# Mother_Board_STM32.net
KiCad netlist of a schematic drawn in Altium Designer
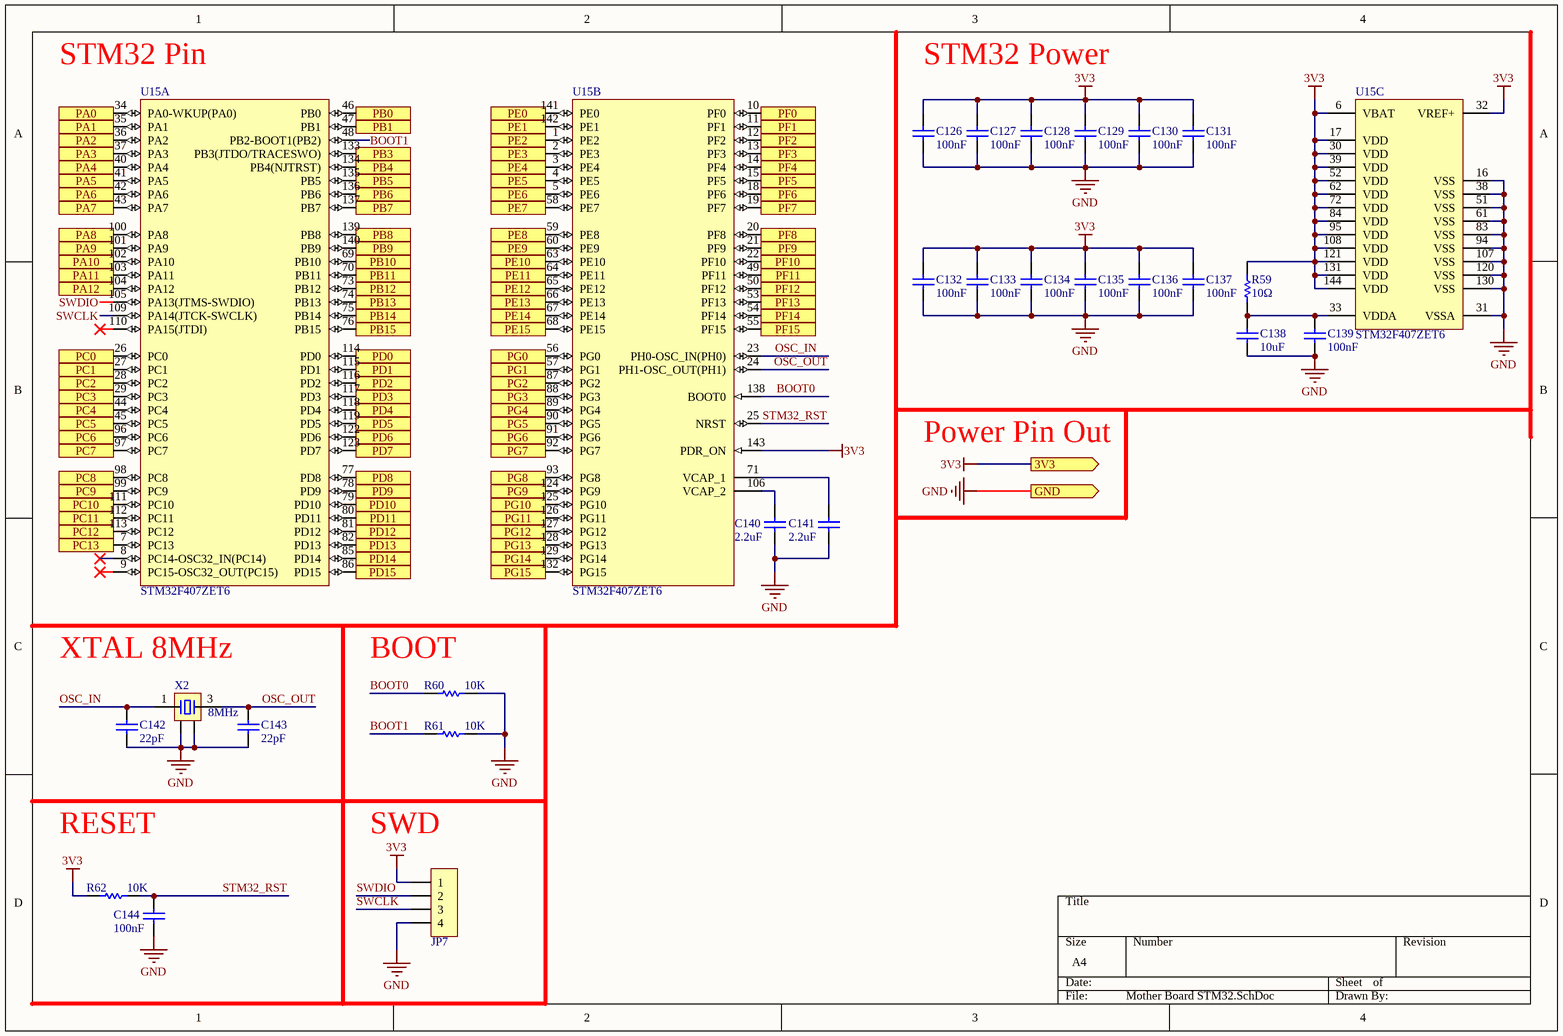
[diagram p0: Mother Board STM32.SchDoc]

(export (version "E")
  (design (tool "Eeschema 10.0.6"))
  (components
    (comp (ref "C126") (value "100nF") (footprint "C0402") (libsource (lib "Cap") (part "Cap")))
    (comp (ref "C127") (value "100nF") (footprint "C0402") (libsource (lib "Cap") (part "Cap")))
    (comp (ref "C128") (value "100nF") (footprint "C0402") (libsource (lib "Cap") (part "Cap")))
    (comp (ref "C129") (value "100nF") (footprint "C0402") (libsource (lib "Cap") (part "Cap")))
    (comp (ref "C130") (value "100nF") (footprint "C0402") (libsource (lib "Cap") (part "Cap")))
    (comp (ref "C131") (value "100nF") (footprint "C0402") (libsource (lib "Cap") (part "Cap")))
    (comp (ref "C132") (value "100nF") (footprint "C0402") (libsource (lib "Cap") (part "Cap")))
    (comp (ref "C133") (value "100nF") (footprint "C0402") (libsource (lib "Cap") (part "Cap")))
    (comp (ref "C134") (value "100nF") (footprint "C0402") (libsource (lib "Cap") (part "Cap")))
    (comp (ref "C135") (value "100nF") (footprint "C0402") (libsource (lib "Cap") (part "Cap")))
    (comp (ref "C136") (value "100nF") (footprint "C0402") (libsource (lib "Cap") (part "Cap")))
    (comp (ref "C137") (value "100nF") (footprint "C0402") (libsource (lib "Cap") (part "Cap")))
    (comp (ref "C138") (value "10uF") (footprint "C0805") (libsource (lib "Cap") (part "Cap")))
    (comp (ref "C139") (value "100nF") (footprint "C0402") (libsource (lib "Cap") (part "Cap")))
    (comp (ref "C140") (value "2.2uF") (footprint "C0603") (libsource (lib "Cap") (part "Cap")))
    (comp (ref "C141") (value "2.2uF") (footprint "C0603") (libsource (lib "Cap") (part "Cap")))
    (comp (ref "C142") (value "22pF") (footprint "C0603") (libsource (lib "Cap") (part "Cap")))
    (comp (ref "C143") (value "22pF") (footprint "C0603") (libsource (lib "Cap") (part "Cap")))
    (comp (ref "C144") (value "100nF") (footprint "C0402") (libsource (lib "Cap") (part "Cap")))
    (comp (ref "JP7")
      (value "HDR-1X4")
      (footprint "XH2.54-4P_H")
      (description "4P接插件")
      (fields (field (name "版权归属") "源创客"))
      (libsource (lib "All lib") (part "Header 4P"))
    )
    (comp (ref "R59") (value "10Ω") (footprint "R0402") (libsource (lib "Res") (part "RES")))
    (comp (ref "R60") (value "10K") (footprint "R0402") (libsource (lib "Res") (part "RES")))
    (comp (ref "R61") (value "10K") (footprint "R0402") (libsource (lib "Res") (part "RES")))
    (comp (ref "R62") (value "10K") (footprint "R0402") (libsource (lib "Res") (part "RES")))
    (comp (ref "U15")
      (value "STM32F407ZET6")
      (footprint "LQFP144 20X20_L")
      (fields (field (name "MANUFACTURER") "STMicroelectronics"))
      (libsource (lib "All lib") (part "STM32F407ZET6"))
    )
    (comp (ref "X2")
      (value "8MHz")
      (footprint "XTAL-3225")
      (description "4脚晶振")
      (fields (field (name "版权归属") "源创客"))
      (libsource (lib "All lib") (part "XTAL-4"))
    )
  )
  (nets
    (net (code "1") (name "/BOOT0") (class "Default")
      (node (ref "R60") (pin "1") (pinfunction "1_1") (pintype "passive"))
      (node (ref "U15") (pin "138") (pinfunction "BOOT0_138") (pintype "input"))
    )
    (net (code "2") (name "/BOOT1") (class "Default")
      (node (ref "R61") (pin "1") (pinfunction "1_1") (pintype "passive"))
      (node (ref "U15") (pin "48") (pinfunction "PB2-BOOT1(PB2)_48") (pintype "bidirectional"))
    )
    (net (code "3") (name "/OSC_IN") (class "Default")
      (node (ref "C142") (pin "2") (pinfunction "2_2") (pintype "passive"))
      (node (ref "U15") (pin "23") (pinfunction "PH0-OSC_IN(PH0)_23") (pintype "bidirectional"))
      (node (ref "X2") (pin "1") (pinfunction "1_1") (pintype "passive"))
    )
    (net (code "4") (name "/OSC_OUT") (class "Default")
      (node (ref "C143") (pin "2") (pinfunction "2_2") (pintype "passive"))
      (node (ref "U15") (pin "24") (pinfunction "PH1-OSC_OUT(PH1)_24") (pintype "bidirectional"))
      (node (ref "X2") (pin "3") (pinfunction "3_3") (pintype "passive"))
    )
    (net (code "5") (name "/PA0") (class "Default")
      (node (ref "U15") (pin "34") (pinfunction "PA0-WKUP(PA0)_34") (pintype "bidirectional"))
    )
    (net (code "6") (name "/PA1") (class "Default")
      (node (ref "U15") (pin "35") (pinfunction "PA1_35") (pintype "bidirectional"))
    )
    (net (code "7") (name "/PA2") (class "Default")
      (node (ref "U15") (pin "36") (pinfunction "PA2_36") (pintype "bidirectional"))
    )
    (net (code "8") (name "/PA3") (class "Default")
      (node (ref "U15") (pin "37") (pinfunction "PA3_37") (pintype "bidirectional"))
    )
    (net (code "9") (name "/PA4") (class "Default")
      (node (ref "U15") (pin "40") (pinfunction "PA4_40") (pintype "bidirectional"))
    )
    (net (code "10") (name "/PA5") (class "Default")
      (node (ref "U15") (pin "41") (pinfunction "PA5_41") (pintype "bidirectional"))
    )
    (net (code "11") (name "/PA6") (class "Default")
      (node (ref "U15") (pin "42") (pinfunction "PA6_42") (pintype "bidirectional"))
    )
    (net (code "12") (name "/PA7") (class "Default")
      (node (ref "U15") (pin "43") (pinfunction "PA7_43") (pintype "bidirectional"))
    )
    (net (code "13") (name "/PA8") (class "Default")
      (node (ref "U15") (pin "100") (pinfunction "PA8_100") (pintype "bidirectional"))
    )
    (net (code "14") (name "/PA9") (class "Default")
      (node (ref "U15") (pin "101") (pinfunction "PA9_101") (pintype "bidirectional"))
    )
    (net (code "15") (name "/PA10") (class "Default")
      (node (ref "U15") (pin "102") (pinfunction "PA10_102") (pintype "bidirectional"))
    )
    (net (code "16") (name "/PA11") (class "Default")
      (node (ref "U15") (pin "103") (pinfunction "PA11_103") (pintype "bidirectional"))
    )
    (net (code "17") (name "/PA12") (class "Default")
      (node (ref "U15") (pin "104") (pinfunction "PA12_104") (pintype "bidirectional"))
    )
    (net (code "18") (name "/PB0") (class "Default")
      (node (ref "U15") (pin "46") (pinfunction "PB0_46") (pintype "bidirectional"))
    )
    (net (code "19") (name "/PB1") (class "Default")
      (node (ref "U15") (pin "47") (pinfunction "PB1_47") (pintype "bidirectional"))
    )
    (net (code "20") (name "/PB3") (class "Default")
      (node (ref "U15") (pin "133") (pinfunction "PB3(JTDO/TRACESWO)_133") (pintype "bidirectional"))
    )
    (net (code "21") (name "/PB4") (class "Default")
      (node (ref "U15") (pin "134") (pinfunction "PB4(NJTRST)_134") (pintype "bidirectional"))
    )
    (net (code "22") (name "/PB5") (class "Default")
      (node (ref "U15") (pin "135") (pinfunction "PB5_135") (pintype "bidirectional"))
    )
    (net (code "23") (name "/PB6") (class "Default")
      (node (ref "U15") (pin "136") (pinfunction "PB6_136") (pintype "bidirectional"))
    )
    (net (code "24") (name "/PB7") (class "Default")
      (node (ref "U15") (pin "137") (pinfunction "PB7_137") (pintype "bidirectional"))
    )
    (net (code "25") (name "/PB8") (class "Default")
      (node (ref "U15") (pin "139") (pinfunction "PB8_139") (pintype "bidirectional"))
    )
    (net (code "26") (name "/PB9") (class "Default")
      (node (ref "U15") (pin "140") (pinfunction "PB9_140") (pintype "bidirectional"))
    )
    (net (code "27") (name "/PB10") (class "Default")
      (node (ref "U15") (pin "69") (pinfunction "PB10_69") (pintype "bidirectional"))
    )
    (net (code "28") (name "/PB11") (class "Default")
      (node (ref "U15") (pin "70") (pinfunction "PB11_70") (pintype "bidirectional"))
    )
    (net (code "29") (name "/PB12") (class "Default")
      (node (ref "U15") (pin "73") (pinfunction "PB12_73") (pintype "bidirectional"))
    )
    (net (code "30") (name "/PB13") (class "Default")
      (node (ref "U15") (pin "74") (pinfunction "PB13_74") (pintype "bidirectional"))
    )
    (net (code "31") (name "/PB14") (class "Default")
      (node (ref "U15") (pin "75") (pinfunction "PB14_75") (pintype "bidirectional"))
    )
    (net (code "32") (name "/PB15") (class "Default")
      (node (ref "U15") (pin "76") (pinfunction "PB15_76") (pintype "bidirectional"))
    )
    (net (code "33") (name "/PC0") (class "Default")
      (node (ref "U15") (pin "26") (pinfunction "PC0_26") (pintype "bidirectional"))
    )
    (net (code "34") (name "/PC1") (class "Default")
      (node (ref "U15") (pin "27") (pinfunction "PC1_27") (pintype "bidirectional"))
    )
    (net (code "35") (name "/PC2") (class "Default")
      (node (ref "U15") (pin "28") (pinfunction "PC2_28") (pintype "bidirectional"))
    )
    (net (code "36") (name "/PC3") (class "Default")
      (node (ref "U15") (pin "29") (pinfunction "PC3_29") (pintype "bidirectional"))
    )
    (net (code "37") (name "/PC4") (class "Default")
      (node (ref "U15") (pin "44") (pinfunction "PC4_44") (pintype "bidirectional"))
    )
    (net (code "38") (name "/PC5") (class "Default")
      (node (ref "U15") (pin "45") (pinfunction "PC5_45") (pintype "bidirectional"))
    )
    (net (code "39") (name "/PC6") (class "Default")
      (node (ref "U15") (pin "96") (pinfunction "PC6_96") (pintype "bidirectional"))
    )
    (net (code "40") (name "/PC7") (class "Default")
      (node (ref "U15") (pin "97") (pinfunction "PC7_97") (pintype "bidirectional"))
    )
    (net (code "41") (name "/PC8") (class "Default")
      (node (ref "U15") (pin "98") (pinfunction "PC8_98") (pintype "bidirectional"))
    )
    (net (code "42") (name "/PC9") (class "Default")
      (node (ref "U15") (pin "99") (pinfunction "PC9_99") (pintype "bidirectional"))
    )
    (net (code "43") (name "/PC10") (class "Default")
      (node (ref "U15") (pin "111") (pinfunction "PC10_111") (pintype "bidirectional"))
    )
    (net (code "44") (name "/PC11") (class "Default")
      (node (ref "U15") (pin "112") (pinfunction "PC11_112") (pintype "bidirectional"))
    )
    (net (code "45") (name "/PC12") (class "Default")
      (node (ref "U15") (pin "113") (pinfunction "PC12_113") (pintype "bidirectional"))
    )
    (net (code "46") (name "/PC13") (class "Default")
      (node (ref "U15") (pin "7") (pinfunction "PC13_7") (pintype "bidirectional"))
    )
    (net (code "47") (name "/PD0") (class "Default")
      (node (ref "U15") (pin "114") (pinfunction "PD0_114") (pintype "bidirectional"))
    )
    (net (code "48") (name "/PD1") (class "Default")
      (node (ref "U15") (pin "115") (pinfunction "PD1_115") (pintype "bidirectional"))
    )
    (net (code "49") (name "/PD2") (class "Default")
      (node (ref "U15") (pin "116") (pinfunction "PD2_116") (pintype "bidirectional"))
    )
    (net (code "50") (name "/PD3") (class "Default")
      (node (ref "U15") (pin "117") (pinfunction "PD3_117") (pintype "bidirectional"))
    )
    (net (code "51") (name "/PD4") (class "Default")
      (node (ref "U15") (pin "118") (pinfunction "PD4_118") (pintype "bidirectional"))
    )
    (net (code "52") (name "/PD5") (class "Default")
      (node (ref "U15") (pin "119") (pinfunction "PD5_119") (pintype "bidirectional"))
    )
    (net (code "53") (name "/PD6") (class "Default")
      (node (ref "U15") (pin "122") (pinfunction "PD6_122") (pintype "bidirectional"))
    )
    (net (code "54") (name "/PD7") (class "Default")
      (node (ref "U15") (pin "123") (pinfunction "PD7_123") (pintype "bidirectional"))
    )
    (net (code "55") (name "/PD8") (class "Default")
      (node (ref "U15") (pin "77") (pinfunction "PD8_77") (pintype "bidirectional"))
    )
    (net (code "56") (name "/PD9") (class "Default")
      (node (ref "U15") (pin "78") (pinfunction "PD9_78") (pintype "bidirectional"))
    )
    (net (code "57") (name "/PD10") (class "Default")
      (node (ref "U15") (pin "79") (pinfunction "PD10_79") (pintype "bidirectional"))
    )
    (net (code "58") (name "/PD11") (class "Default")
      (node (ref "U15") (pin "80") (pinfunction "PD11_80") (pintype "bidirectional"))
    )
    (net (code "59") (name "/PD12") (class "Default")
      (node (ref "U15") (pin "81") (pinfunction "PD12_81") (pintype "bidirectional"))
    )
    (net (code "60") (name "/PD13") (class "Default")
      (node (ref "U15") (pin "82") (pinfunction "PD13_82") (pintype "bidirectional"))
    )
    (net (code "61") (name "/PD14") (class "Default")
      (node (ref "U15") (pin "85") (pinfunction "PD14_85") (pintype "bidirectional"))
    )
    (net (code "62") (name "/PD15") (class "Default")
      (node (ref "U15") (pin "86") (pinfunction "PD15_86") (pintype "bidirectional"))
    )
    (net (code "63") (name "/PE0") (class "Default")
      (node (ref "U15") (pin "141") (pinfunction "PE0_141") (pintype "bidirectional"))
    )
    (net (code "64") (name "/PE1") (class "Default")
      (node (ref "U15") (pin "142") (pinfunction "PE1_142") (pintype "bidirectional"))
    )
    (net (code "65") (name "/PE2") (class "Default")
      (node (ref "U15") (pin "1") (pinfunction "PE2_1") (pintype "bidirectional"))
    )
    (net (code "66") (name "/PE3") (class "Default")
      (node (ref "U15") (pin "2") (pinfunction "PE3_2") (pintype "bidirectional"))
    )
    (net (code "67") (name "/PE4") (class "Default")
      (node (ref "U15") (pin "3") (pinfunction "PE4_3") (pintype "bidirectional"))
    )
    (net (code "68") (name "/PE5") (class "Default")
      (node (ref "U15") (pin "4") (pinfunction "PE5_4") (pintype "bidirectional"))
    )
    (net (code "69") (name "/PE6") (class "Default")
      (node (ref "U15") (pin "5") (pinfunction "PE6_5") (pintype "bidirectional"))
    )
    (net (code "70") (name "/PE7") (class "Default")
      (node (ref "U15") (pin "58") (pinfunction "PE7_58") (pintype "bidirectional"))
    )
    (net (code "71") (name "/PE8") (class "Default")
      (node (ref "U15") (pin "59") (pinfunction "PE8_59") (pintype "bidirectional"))
    )
    (net (code "72") (name "/PE9") (class "Default")
      (node (ref "U15") (pin "60") (pinfunction "PE9_60") (pintype "bidirectional"))
    )
    (net (code "73") (name "/PE10") (class "Default")
      (node (ref "U15") (pin "63") (pinfunction "PE10_63") (pintype "bidirectional"))
    )
    (net (code "74") (name "/PE11") (class "Default")
      (node (ref "U15") (pin "64") (pinfunction "PE11_64") (pintype "bidirectional"))
    )
    (net (code "75") (name "/PE12") (class "Default")
      (node (ref "U15") (pin "65") (pinfunction "PE12_65") (pintype "bidirectional"))
    )
    (net (code "76") (name "/PE13") (class "Default")
      (node (ref "U15") (pin "66") (pinfunction "PE13_66") (pintype "bidirectional"))
    )
    (net (code "77") (name "/PE14") (class "Default")
      (node (ref "U15") (pin "67") (pinfunction "PE14_67") (pintype "bidirectional"))
    )
    (net (code "78") (name "/PE15") (class "Default")
      (node (ref "U15") (pin "68") (pinfunction "PE15_68") (pintype "bidirectional"))
    )
    (net (code "79") (name "/PF0") (class "Default")
      (node (ref "U15") (pin "10") (pinfunction "PF0_10") (pintype "bidirectional"))
    )
    (net (code "80") (name "/PF1") (class "Default")
      (node (ref "U15") (pin "11") (pinfunction "PF1_11") (pintype "bidirectional"))
    )
    (net (code "81") (name "/PF2") (class "Default")
      (node (ref "U15") (pin "12") (pinfunction "PF2_12") (pintype "bidirectional"))
    )
    (net (code "82") (name "/PF3") (class "Default")
      (node (ref "U15") (pin "13") (pinfunction "PF3_13") (pintype "bidirectional"))
    )
    (net (code "83") (name "/PF4") (class "Default")
      (node (ref "U15") (pin "14") (pinfunction "PF4_14") (pintype "bidirectional"))
    )
    (net (code "84") (name "/PF5") (class "Default")
      (node (ref "U15") (pin "15") (pinfunction "PF5_15") (pintype "bidirectional"))
    )
    (net (code "85") (name "/PF6") (class "Default")
      (node (ref "U15") (pin "18") (pinfunction "PF6_18") (pintype "bidirectional"))
    )
    (net (code "86") (name "/PF7") (class "Default")
      (node (ref "U15") (pin "19") (pinfunction "PF7_19") (pintype "bidirectional"))
    )
    (net (code "87") (name "/PF8") (class "Default")
      (node (ref "U15") (pin "20") (pinfunction "PF8_20") (pintype "bidirectional"))
    )
    (net (code "88") (name "/PF9") (class "Default")
      (node (ref "U15") (pin "21") (pinfunction "PF9_21") (pintype "bidirectional"))
    )
    (net (code "89") (name "/PF10") (class "Default")
      (node (ref "U15") (pin "22") (pinfunction "PF10_22") (pintype "bidirectional"))
    )
    (net (code "90") (name "/PF11") (class "Default")
      (node (ref "U15") (pin "49") (pinfunction "PF11_49") (pintype "bidirectional"))
    )
    (net (code "91") (name "/PF12") (class "Default")
      (node (ref "U15") (pin "50") (pinfunction "PF12_50") (pintype "bidirectional"))
    )
    (net (code "92") (name "/PF13") (class "Default")
      (node (ref "U15") (pin "53") (pinfunction "PF13_53") (pintype "bidirectional"))
    )
    (net (code "93") (name "/PF14") (class "Default")
      (node (ref "U15") (pin "54") (pinfunction "PF14_54") (pintype "bidirectional"))
    )
    (net (code "94") (name "/PF15") (class "Default")
      (node (ref "U15") (pin "55") (pinfunction "PF15_55") (pintype "bidirectional"))
    )
    (net (code "95") (name "/PG0") (class "Default")
      (node (ref "U15") (pin "56") (pinfunction "PG0_56") (pintype "bidirectional"))
    )
    (net (code "96") (name "/PG1") (class "Default")
      (node (ref "U15") (pin "57") (pinfunction "PG1_57") (pintype "bidirectional"))
    )
    (net (code "97") (name "/PG2") (class "Default")
      (node (ref "U15") (pin "87") (pinfunction "PG2_87") (pintype "bidirectional"))
    )
    (net (code "98") (name "/PG3") (class "Default")
      (node (ref "U15") (pin "88") (pinfunction "PG3_88") (pintype "bidirectional"))
    )
    (net (code "99") (name "/PG4") (class "Default")
      (node (ref "U15") (pin "89") (pinfunction "PG4_89") (pintype "bidirectional"))
    )
    (net (code "100") (name "/PG5") (class "Default")
      (node (ref "U15") (pin "90") (pinfunction "PG5_90") (pintype "bidirectional"))
    )
    (net (code "101") (name "/PG6") (class "Default")
      (node (ref "U15") (pin "91") (pinfunction "PG6_91") (pintype "bidirectional"))
    )
    (net (code "102") (name "/PG7") (class "Default")
      (node (ref "U15") (pin "92") (pinfunction "PG7_92") (pintype "bidirectional"))
    )
    (net (code "103") (name "/PG8") (class "Default")
      (node (ref "U15") (pin "93") (pinfunction "PG8_93") (pintype "bidirectional"))
    )
    (net (code "104") (name "/PG9") (class "Default")
      (node (ref "U15") (pin "124") (pinfunction "PG9_124") (pintype "bidirectional"))
    )
    (net (code "105") (name "/PG10") (class "Default")
      (node (ref "U15") (pin "125") (pinfunction "PG10_125") (pintype "bidirectional"))
    )
    (net (code "106") (name "/PG11") (class "Default")
      (node (ref "U15") (pin "126") (pinfunction "PG11_126") (pintype "bidirectional"))
    )
    (net (code "107") (name "/PG12") (class "Default")
      (node (ref "U15") (pin "127") (pinfunction "PG12_127") (pintype "bidirectional"))
    )
    (net (code "108") (name "/PG13") (class "Default")
      (node (ref "U15") (pin "128") (pinfunction "PG13_128") (pintype "bidirectional"))
    )
    (net (code "109") (name "/PG14") (class "Default")
      (node (ref "U15") (pin "129") (pinfunction "PG14_129") (pintype "bidirectional"))
    )
    (net (code "110") (name "/PG15") (class "Default")
      (node (ref "U15") (pin "132") (pinfunction "PG15_132") (pintype "bidirectional"))
    )
    (net (code "111") (name "/STM32_RST") (class "Default")
      (node (ref "C144") (pin "2") (pinfunction "2_2") (pintype "passive"))
      (node (ref "R62") (pin "2") (pinfunction "2_2") (pintype "passive"))
      (node (ref "U15") (pin "25") (pinfunction "NRST_25") (pintype "bidirectional"))
    )
    (net (code "112") (name "/SWCLK") (class "Default")
      (node (ref "JP7") (pin "3") (pinfunction "3_3") (pintype "passive"))
      (node (ref "U15") (pin "109") (pinfunction "PA14(JTCK-SWCLK)_109") (pintype "bidirectional"))
    )
    (net (code "113") (name "/SWDIO") (class "Default")
      (node (ref "JP7") (pin "2") (pinfunction "2_2") (pintype "passive"))
      (node (ref "U15") (pin "105") (pinfunction "PA13(JTMS-SWDIO)_105") (pintype "bidirectional"))
    )
    (net (code "114") (name "3V3") (class "Default")
      (node (ref "C126") (pin "1") (pinfunction "1_1") (pintype "passive"))
      (node (ref "C127") (pin "1") (pinfunction "1_1") (pintype "passive"))
      (node (ref "C128") (pin "1") (pinfunction "1_1") (pintype "passive"))
      (node (ref "C129") (pin "1") (pinfunction "1_1") (pintype "passive"))
      (node (ref "C130") (pin "1") (pinfunction "1_1") (pintype "passive"))
      (node (ref "C131") (pin "1") (pinfunction "1_1") (pintype "passive"))
      (node (ref "C132") (pin "1") (pinfunction "1_1") (pintype "passive"))
      (node (ref "C133") (pin "1") (pinfunction "1_1") (pintype "passive"))
      (node (ref "C134") (pin "1") (pinfunction "1_1") (pintype "passive"))
      (node (ref "C135") (pin "1") (pinfunction "1_1") (pintype "passive"))
      (node (ref "C136") (pin "1") (pinfunction "1_1") (pintype "passive"))
      (node (ref "C137") (pin "1") (pinfunction "1_1") (pintype "passive"))
      (node (ref "JP7") (pin "1") (pinfunction "1_1") (pintype "passive"))
      (node (ref "R59") (pin "2") (pinfunction "2_2") (pintype "passive"))
      (node (ref "R62") (pin "1") (pinfunction "1_1") (pintype "passive"))
      (node (ref "U15") (pin "108") (pinfunction "VDD_108") (pintype "power_in"))
      (node (ref "U15") (pin "121") (pinfunction "VDD_121") (pintype "power_in"))
      (node (ref "U15") (pin "131") (pinfunction "VDD_131") (pintype "power_in"))
      (node (ref "U15") (pin "143") (pinfunction "PDR_ON_143") (pintype "input"))
      (node (ref "U15") (pin "144") (pinfunction "VDD_144") (pintype "power_in"))
      (node (ref "U15") (pin "17") (pinfunction "VDD_17") (pintype "power_in"))
      (node (ref "U15") (pin "30") (pinfunction "VDD_30") (pintype "power_in"))
      (node (ref "U15") (pin "32") (pinfunction "VREF+_32") (pintype "power_in"))
      (node (ref "U15") (pin "39") (pinfunction "VDD_39") (pintype "power_in"))
      (node (ref "U15") (pin "52") (pinfunction "VDD_52") (pintype "power_in"))
      (node (ref "U15") (pin "6") (pinfunction "VBAT_6") (pintype "power_in"))
      (node (ref "U15") (pin "62") (pinfunction "VDD_62") (pintype "power_in"))
      (node (ref "U15") (pin "72") (pinfunction "VDD_72") (pintype "power_in"))
      (node (ref "U15") (pin "84") (pinfunction "VDD_84") (pintype "power_in"))
      (node (ref "U15") (pin "95") (pinfunction "VDD_95") (pintype "power_in"))
    )
    (net (code "115") (name "GND") (class "Default")
      (node (ref "C126") (pin "2") (pinfunction "2_2") (pintype "passive"))
      (node (ref "C127") (pin "2") (pinfunction "2_2") (pintype "passive"))
      (node (ref "C128") (pin "2") (pinfunction "2_2") (pintype "passive"))
      (node (ref "C129") (pin "2") (pinfunction "2_2") (pintype "passive"))
      (node (ref "C130") (pin "2") (pinfunction "2_2") (pintype "passive"))
      (node (ref "C131") (pin "2") (pinfunction "2_2") (pintype "passive"))
      (node (ref "C132") (pin "2") (pinfunction "2_2") (pintype "passive"))
      (node (ref "C133") (pin "2") (pinfunction "2_2") (pintype "passive"))
      (node (ref "C134") (pin "2") (pinfunction "2_2") (pintype "passive"))
      (node (ref "C135") (pin "2") (pinfunction "2_2") (pintype "passive"))
      (node (ref "C136") (pin "2") (pinfunction "2_2") (pintype "passive"))
      (node (ref "C137") (pin "2") (pinfunction "2_2") (pintype "passive"))
      (node (ref "C138") (pin "2") (pinfunction "2_2") (pintype "passive"))
      (node (ref "C139") (pin "2") (pinfunction "2_2") (pintype "passive"))
      (node (ref "C140") (pin "1") (pinfunction "1_1") (pintype "passive"))
      (node (ref "C141") (pin "1") (pinfunction "1_1") (pintype "passive"))
      (node (ref "C142") (pin "1") (pinfunction "1_1") (pintype "passive"))
      (node (ref "C143") (pin "1") (pinfunction "1_1") (pintype "passive"))
      (node (ref "C144") (pin "1") (pinfunction "1_1") (pintype "passive"))
      (node (ref "JP7") (pin "4") (pinfunction "4_4") (pintype "passive"))
      (node (ref "R60") (pin "2") (pinfunction "2_2") (pintype "passive"))
      (node (ref "R61") (pin "2") (pinfunction "2_2") (pintype "passive"))
      (node (ref "U15") (pin "107") (pinfunction "VSS_107") (pintype "power_in"))
      (node (ref "U15") (pin "120") (pinfunction "VSS_120") (pintype "power_in"))
      (node (ref "U15") (pin "130") (pinfunction "VSS_130") (pintype "power_in"))
      (node (ref "U15") (pin "16") (pinfunction "VSS_16") (pintype "power_in"))
      (node (ref "U15") (pin "31") (pinfunction "VSSA_31") (pintype "power_in"))
      (node (ref "U15") (pin "38") (pinfunction "VSS_38") (pintype "power_in"))
      (node (ref "U15") (pin "51") (pinfunction "VSS_51") (pintype "power_in"))
      (node (ref "U15") (pin "61") (pinfunction "VSS_61") (pintype "power_in"))
      (node (ref "U15") (pin "83") (pinfunction "VSS_83") (pintype "power_in"))
      (node (ref "U15") (pin "94") (pinfunction "VSS_94") (pintype "power_in"))
      (node (ref "X2") (pin "2") (pinfunction "2_2") (pintype "passive"))
      (node (ref "X2") (pin "4") (pinfunction "4_4") (pintype "passive"))
    )
    (net (code "116") (name "Net-(U15B-VCAP_1)") (class "Default")
      (node (ref "C141") (pin "2") (pinfunction "2_2") (pintype "passive"))
      (node (ref "U15") (pin "71") (pinfunction "VCAP_1_71") (pintype "power_in"))
    )
    (net (code "117") (name "Net-(U15B-VCAP_2)") (class "Default")
      (node (ref "C140") (pin "2") (pinfunction "2_2") (pintype "passive"))
      (node (ref "U15") (pin "106") (pinfunction "VCAP_2_106") (pintype "power_in"))
    )
    (net (code "118") (name "Net-(U15C-VDDA)") (class "Default")
      (node (ref "C138") (pin "1") (pinfunction "1_1") (pintype "passive"))
      (node (ref "C139") (pin "1") (pinfunction "1_1") (pintype "passive"))
      (node (ref "R59") (pin "1") (pinfunction "1_1") (pintype "passive"))
      (node (ref "U15") (pin "33") (pinfunction "VDDA_33") (pintype "power_in"))
    )
    (net (code "119") (name "unconnected-(U15A-PA15(JTDI)-Pad110)") (class "Default")
      (node (ref "U15") (pin "110") (pinfunction "PA15(JTDI)_110") (pintype "bidirectional+no_connect"))
    )
    (net (code "120") (name "unconnected-(U15A-PC14-OSC32_IN(PC14)-Pad8)") (class "Default")
      (node (ref "U15") (pin "8") (pinfunction "PC14-OSC32_IN(PC14)_8") (pintype "bidirectional+no_connect"))
    )
    (net (code "121") (name "unconnected-(U15A-PC15-OSC32_OUT(PC15)-Pad9)") (class "Default")
      (node (ref "U15") (pin "9") (pinfunction "PC15-OSC32_OUT(PC15)_9") (pintype "bidirectional+no_connect"))
    )
  )
)
